# SDCARD.net
KiCad netlist of a schematic drawn in Altium Designer
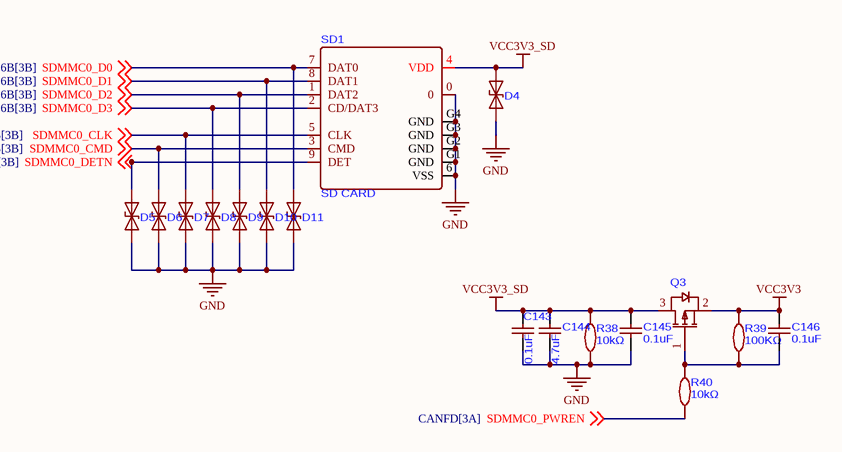
[diagram p0: SDCARD.SchDoc]

(export (version "E")
  (design (tool "Eeschema 10.0.6"))
  (components
    (comp (ref "C143")
      (value "0.1uF")
      (footprint "C0201")
      (description "0.1uF ±10% 6.3V Ceramic Capacitor X5R 0201")
      (libsource (lib "Schlib1") (part "CAP_100nF-6.3V-10%-0201_1"))
    )
    (comp (ref "C144")
      (value "4.7uF")
      (footprint "C0402")
      (description "4.7uF ±10% 16V Ceramic Capacitor X5R 0402")
      (libsource (lib "Schlib1") (part "CAP_4.7uF-16V-10%-0402"))
    )
    (comp (ref "C145")
      (value "0.1uF")
      (footprint "C0201")
      (description "0.1uF ±10% 6.3V Ceramic Capacitor X5R 0201")
      (libsource (lib "Schlib1") (part "CAP_100nF-6.3V-10%-0201_1"))
    )
    (comp (ref "C146")
      (value "0.1uF")
      (footprint "C0201")
      (description "0.1uF ±10% 6.3V Ceramic Capacitor X5R 0201")
      (libsource (lib "Schlib1") (part "CAP_100nF-6.3V-10%-0201_1"))
    )
    (comp (ref "D4")
      (value "ESD DIODE")
      (footprint "DSN0603-2_L0.7-W0.3-P0.40-BI")
      (description "ESD DIODE 5VWM 5VC DSN0603-2 0.13PF")
      (libsource (lib "Schlib1") (part "PESD5V0H1BSFYL"))
    )
    (comp (ref "D5")
      (value "ESD DIODE")
      (footprint "DSN0603-2_L0.7-W0.3-P0.40-BI")
      (description "ESD DIODE 5VWM 5VC DSN0603-2 0.13PF")
      (libsource (lib "Schlib1") (part "PESD5V0H1BSFYL"))
    )
    (comp (ref "D6")
      (value "ESD DIODE")
      (footprint "DSN0603-2_L0.7-W0.3-P0.40-BI")
      (description "ESD DIODE 5VWM 5VC DSN0603-2 0.13PF")
      (libsource (lib "Schlib1") (part "PESD5V0H1BSFYL"))
    )
    (comp (ref "D7")
      (value "ESD DIODE")
      (footprint "DSN0603-2_L0.7-W0.3-P0.40-BI")
      (description "ESD DIODE 5VWM 5VC DSN0603-2 0.13PF")
      (libsource (lib "Schlib1") (part "PESD5V0H1BSFYL"))
    )
    (comp (ref "D8")
      (value "ESD DIODE")
      (footprint "DSN0603-2_L0.7-W0.3-P0.40-BI")
      (description "ESD DIODE 5VWM 5VC DSN0603-2 0.13PF")
      (libsource (lib "Schlib1") (part "PESD5V0H1BSFYL"))
    )
    (comp (ref "D9")
      (value "ESD DIODE")
      (footprint "DSN0603-2_L0.7-W0.3-P0.40-BI")
      (description "ESD DIODE 5VWM 5VC DSN0603-2 0.13PF")
      (libsource (lib "Schlib1") (part "PESD5V0H1BSFYL"))
    )
    (comp (ref "D10")
      (value "ESD DIODE")
      (footprint "DSN0603-2_L0.7-W0.3-P0.40-BI")
      (description "ESD DIODE 5VWM 5VC DSN0603-2 0.13PF")
      (libsource (lib "Schlib1") (part "PESD5V0H1BSFYL"))
    )
    (comp (ref "D11")
      (value "ESD DIODE")
      (footprint "DSN0603-2_L0.7-W0.3-P0.40-BI")
      (description "ESD DIODE 5VWM 5VC DSN0603-2 0.13PF")
      (libsource (lib "Schlib1") (part "PESD5V0H1BSFYL"))
    )
    (comp (ref "Q3")
      (value "P-CHANNEL")
      (footprint "SOT-23-3_L2.9-W1.3-P1.90-LS2.4-BR")
      (description "MOSFET P-CH 30V 4.4A SOT-23")
      (libsource (lib "Schlib1") (part "WPM3407-3/TR"))
    )
    (comp (ref "R38")
      (value "10kΩ")
      (footprint "R0201")
      (description "RES 10KΩ ±1% 50mW 0201")
      (libsource (lib "Schlib1") (part "RES_10K-50mW-1%-0201"))
    )
    (comp (ref "R39")
      (value "100KΩ")
      (footprint "R0201")
      (description "RES 100kΩ ±1% 50mW 0201")
      (libsource (lib "Schlib1") (part "RES_100K-50mW-1%-0201"))
    )
    (comp (ref "R40")
      (value "10kΩ")
      (footprint "R0201")
      (description "RES 10KΩ ±1% 50mW 0201")
      (libsource (lib "Schlib1") (part "RES_10K-50mW-1%-0201"))
    )
    (comp (ref "SD1")
      (value "SD CARD")
      (footprint "CONN-SMD_1051620101")
      (description "CONN MICRO SD CARD (TF CARD)")
      (libsource (lib "Schlib1") (part "1051620001"))
    )
  )
  (nets
    (net (code "1") (name "GND") (class "Default")
      (node (ref "C143") (pin "1") (pinfunction "1_1") (pintype "passive"))
      (node (ref "C144") (pin "1") (pinfunction "1_1") (pintype "passive"))
      (node (ref "C145") (pin "1") (pinfunction "1_1") (pintype "passive"))
      (node (ref "D10") (pin "1") (pinfunction "K_1") (pintype "passive"))
      (node (ref "D11") (pin "1") (pinfunction "K_1") (pintype "passive"))
      (node (ref "D4") (pin "1") (pinfunction "K_1") (pintype "passive"))
      (node (ref "D5") (pin "1") (pinfunction "K_1") (pintype "passive"))
      (node (ref "D6") (pin "1") (pinfunction "K_1") (pintype "passive"))
      (node (ref "D7") (pin "1") (pinfunction "K_1") (pintype "passive"))
      (node (ref "D8") (pin "1") (pinfunction "K_1") (pintype "passive"))
      (node (ref "D9") (pin "1") (pinfunction "K_1") (pintype "passive"))
      (node (ref "R38") (pin "1") (pinfunction "1_1") (pintype "passive"))
      (node (ref "SD1") (pin "0") (pinfunction "0_0") (pintype "passive"))
      (node (ref "SD1") (pin "6") (pinfunction "VSS_6") (pintype "passive"))
      (node (ref "SD1") (pin "G1") (pinfunction "GND_G1") (pintype "passive"))
      (node (ref "SD1") (pin "G2") (pinfunction "GND_G2") (pintype "passive"))
      (node (ref "SD1") (pin "G3") (pinfunction "GND_G3") (pintype "passive"))
      (node (ref "SD1") (pin "G4") (pinfunction "GND_G4") (pintype "passive"))
    )
    (net (code "2") (name "Net-(Q3-G)") (class "Default")
      (node (ref "C146") (pin "1") (pinfunction "1_1") (pintype "passive"))
      (node (ref "Q3") (pin "1") (pinfunction "G_1") (pintype "passive"))
      (node (ref "R39") (pin "1") (pinfunction "1_1") (pintype "passive"))
      (node (ref "R40") (pin "2") (pinfunction "2_2") (pintype "passive"))
    )
    (net (code "3") (name "SDMMC0_CLK") (class "Default")
      (node (ref "D7") (pin "2") (pinfunction "A_2") (pintype "passive"))
      (node (ref "SD1") (pin "5") (pinfunction "CLK_5") (pintype "passive"))
    )
    (net (code "4") (name "SDMMC0_CMD") (class "Default")
      (node (ref "D6") (pin "2") (pinfunction "A_2") (pintype "passive"))
      (node (ref "SD1") (pin "3") (pinfunction "CMD_3") (pintype "passive"))
    )
    (net (code "5") (name "SDMMC0_D0") (class "Default")
      (node (ref "D11") (pin "2") (pinfunction "A_2") (pintype "passive"))
      (node (ref "SD1") (pin "7") (pinfunction "DAT0_7") (pintype "passive"))
    )
    (net (code "6") (name "SDMMC0_D1") (class "Default")
      (node (ref "D10") (pin "2") (pinfunction "A_2") (pintype "passive"))
      (node (ref "SD1") (pin "8") (pinfunction "DAT1_8") (pintype "passive"))
    )
    (net (code "7") (name "SDMMC0_D2") (class "Default")
      (node (ref "D9") (pin "2") (pinfunction "A_2") (pintype "passive"))
      (node (ref "SD1") (pin "1") (pinfunction "DAT2_1") (pintype "passive"))
    )
    (net (code "8") (name "SDMMC0_D3") (class "Default")
      (node (ref "D8") (pin "2") (pinfunction "A_2") (pintype "passive"))
      (node (ref "SD1") (pin "2") (pinfunction "CD/DAT3_2") (pintype "passive"))
    )
    (net (code "9") (name "SDMMC0_DETN") (class "Default")
      (node (ref "D5") (pin "2") (pinfunction "A_2") (pintype "passive"))
      (node (ref "SD1") (pin "9") (pinfunction "DET_9") (pintype "passive"))
    )
    (net (code "10") (name "SDMMC0_PWREN") (class "Default")
      (node (ref "R40") (pin "1") (pinfunction "1_1") (pintype "passive"))
    )
    (net (code "11") (name "VCC3V3") (class "Default")
      (node (ref "C146") (pin "2") (pinfunction "2_2") (pintype "passive"))
      (node (ref "Q3") (pin "2") (pinfunction "S_2") (pintype "passive"))
      (node (ref "R39") (pin "2") (pinfunction "2_2") (pintype "passive"))
    )
    (net (code "12") (name "VCC3V3_SD") (class "Default")
      (node (ref "C143") (pin "2") (pinfunction "2_2") (pintype "passive"))
      (node (ref "C144") (pin "2") (pinfunction "2_2") (pintype "passive"))
      (node (ref "C145") (pin "2") (pinfunction "2_2") (pintype "passive"))
      (node (ref "D4") (pin "2") (pinfunction "A_2") (pintype "passive"))
      (node (ref "Q3") (pin "3") (pinfunction "D_3") (pintype "passive"))
      (node (ref "R38") (pin "2") (pinfunction "2_2") (pintype "passive"))
      (node (ref "SD1") (pin "4") (pinfunction "VDD_4") (pintype "passive"))
    )
  )
)
